# uPre.net
KiCad netlist of a schematic drawn in Altium Designer
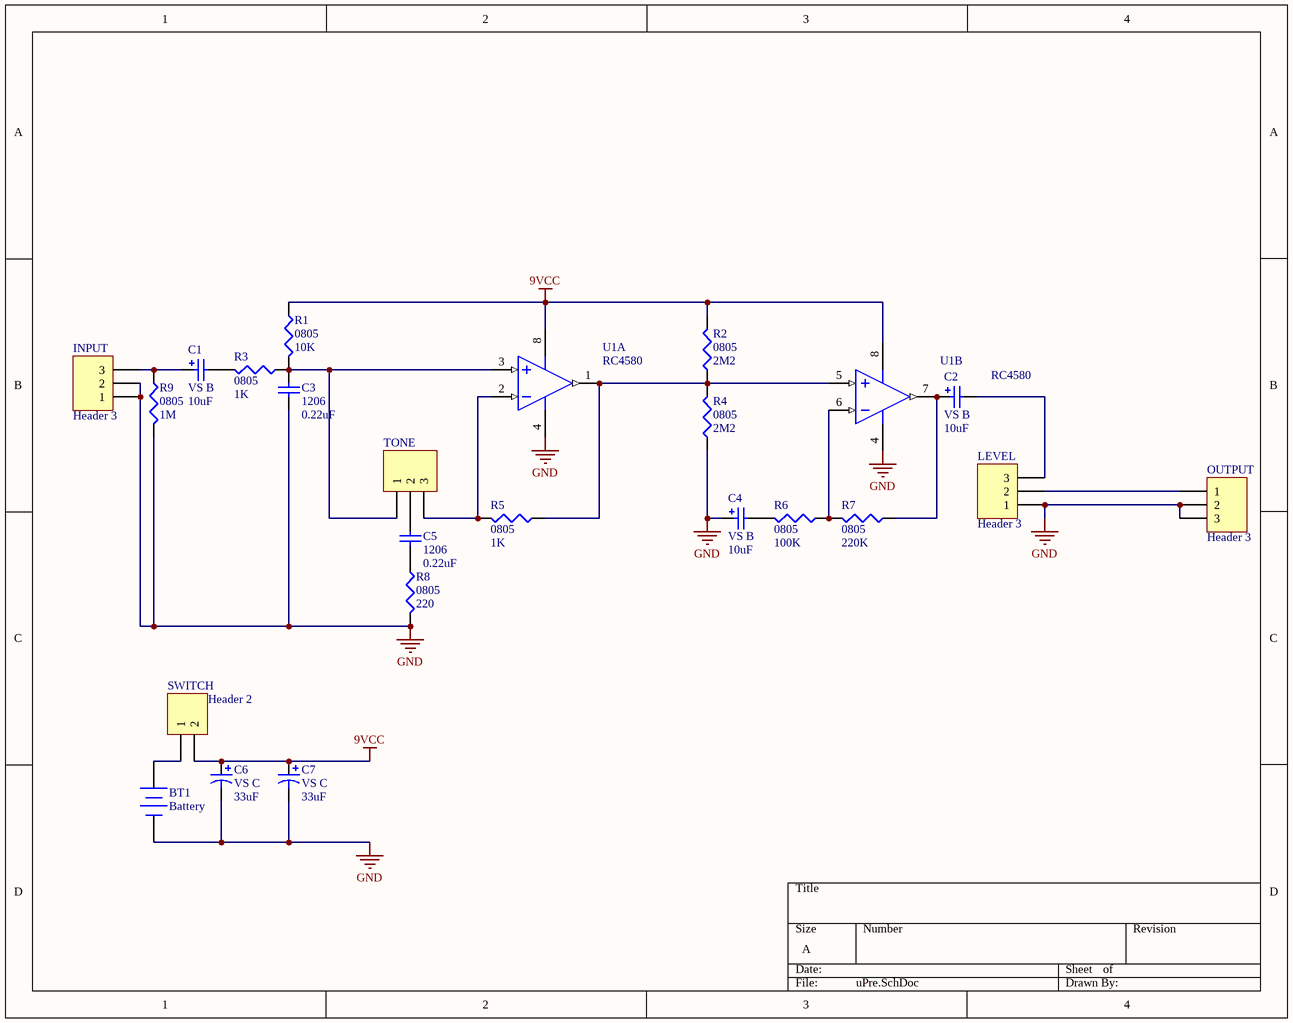
[diagram p0: uPre.SchDoc]

(export (version "E")
  (design (tool "Eeschema 10.0.6"))
  (components
    (comp (ref "BT1")
      (value "Battery")
      (footprint "BAT-2")
      (description "Multicell Battery")
      (fields (field (name "PUBLISHER") "Altium Limited"))
      (libsource (lib "Miscellaneous Devices") (part "Battery"))
    )
    (comp (ref "C1")
      (value "VS B")
      (footprint "Panasonic VS B")
      (description "Polarized Capacitor (Axial)")
      (fields (field (name "ALTIUM_VALUE") "10uF") (field (name "PUBLISHER") "Altium Limited"))
      (libsource (lib "Miscellaneous Devices") (part "Cap Pol2"))
    )
    (comp (ref "C2")
      (value "VS B")
      (footprint "Panasonic VS B")
      (description "Polarized Capacitor (Axial)")
      (fields (field (name "ALTIUM_VALUE") "10uF") (field (name "PUBLISHER") "Altium Limited"))
      (libsource (lib "Miscellaneous Devices") (part "Cap Pol2"))
    )
    (comp (ref "C3")
      (value "1206")
      (footprint "C1206")
      (description "Capacitor (Semiconductor SIM Model)")
      (fields (field (name "ALTIUM_VALUE") "0.22uF") (field (name "PUBLISHER") "Altium Limited"))
      (libsource (lib "Miscellaneous Devices") (part "Cap Semi"))
    )
    (comp (ref "C4")
      (value "VS B")
      (footprint "Panasonic VS B")
      (description "Polarized Capacitor (Axial)")
      (fields (field (name "ALTIUM_VALUE") "10uF") (field (name "PUBLISHER") "Altium Limited"))
      (libsource (lib "Miscellaneous Devices") (part "Cap Pol2"))
    )
    (comp (ref "C5")
      (value "1206")
      (footprint "C1206")
      (description "Capacitor (Semiconductor SIM Model)")
      (fields (field (name "ALTIUM_VALUE") "0.22uF") (field (name "PUBLISHER") "Altium Limited"))
      (libsource (lib "Miscellaneous Devices") (part "Cap Semi"))
    )
    (comp (ref "C6")
      (value "VS C")
      (footprint "Panasonic VS C")
      (description "Polarized Capacitor (Radial)")
      (fields (field (name "ALTIUM_VALUE") "33uF") (field (name "PUBLISHER") "Altium Limited"))
      (libsource (lib "Miscellaneous Devices") (part "Cap Pol1"))
    )
    (comp (ref "C7")
      (value "VS C")
      (footprint "Panasonic VS C")
      (description "Polarized Capacitor (Radial)")
      (fields (field (name "ALTIUM_VALUE") "33uF") (field (name "PUBLISHER") "Altium Limited"))
      (libsource (lib "Miscellaneous Devices") (part "Cap Pol1"))
    )
    (comp (ref "INPUT")
      (value "Header 3")
      (footprint "HDR1X3")
      (description "Header, 3-Pin")
      (fields (field (name "PUBLISHER") "Altium Limited"))
      (libsource (lib "") (part "Header 3_1"))
    )
    (comp (ref "LEVEL")
      (value "Header 3")
      (footprint "HDR1X3")
      (description "Header, 3-Pin")
      (fields (field (name "PUBLISHER") "Altium Limited"))
      (libsource (lib "") (part "Header 3_1"))
    )
    (comp (ref "OUTPUT")
      (value "Header 3")
      (footprint "HDR1X3")
      (description "Header, 3-Pin")
      (fields (field (name "PUBLISHER") "Altium Limited"))
      (libsource (lib "Miscellaneous Connectors") (part "Header 3"))
    )
    (comp (ref "R1")
      (value "0805")
      (footprint "SM 0805 - gap trimmed")
      (description "Resistor")
      (fields (field (name "ALTIUM_VALUE") "10K") (field (name "PUBLISHER") "Altium Limited"))
      (libsource (lib "Miscellaneous Devices") (part "Res3"))
    )
    (comp (ref "R2")
      (value "0805")
      (footprint "SM 0805 - gap trimmed")
      (description "Resistor")
      (fields (field (name "ALTIUM_VALUE") "2M2") (field (name "PUBLISHER") "Altium Limited"))
      (libsource (lib "Miscellaneous Devices") (part "Res3"))
    )
    (comp (ref "R3")
      (value "0805")
      (footprint "SM 0805 - gap trimmed")
      (description "Resistor")
      (fields (field (name "ALTIUM_VALUE") "1K") (field (name "PUBLISHER") "Altium Limited"))
      (libsource (lib "Miscellaneous Devices") (part "Res3"))
    )
    (comp (ref "R4")
      (value "0805")
      (footprint "SM 0805 - gap trimmed")
      (description "Resistor")
      (fields (field (name "ALTIUM_VALUE") "2M2") (field (name "PUBLISHER") "Altium Limited"))
      (libsource (lib "Miscellaneous Devices") (part "Res3"))
    )
    (comp (ref "R5")
      (value "0805")
      (footprint "SM 0805 - gap trimmed")
      (description "Resistor")
      (fields (field (name "ALTIUM_VALUE") "1K") (field (name "PUBLISHER") "Altium Limited"))
      (libsource (lib "Miscellaneous Devices") (part "Res3"))
    )
    (comp (ref "R6")
      (value "0805")
      (footprint "SM 0805 - gap trimmed")
      (description "Resistor")
      (fields (field (name "ALTIUM_VALUE") "100K") (field (name "PUBLISHER") "Altium Limited"))
      (libsource (lib "Miscellaneous Devices") (part "Res3"))
    )
    (comp (ref "R7")
      (value "0805")
      (footprint "SM 0805 - gap trimmed")
      (description "Resistor")
      (fields (field (name "ALTIUM_VALUE") "220K") (field (name "PUBLISHER") "Altium Limited"))
      (libsource (lib "Miscellaneous Devices") (part "Res3"))
    )
    (comp (ref "R8")
      (value "0805")
      (footprint "SM 0805 - gap trimmed")
      (description "Resistor")
      (fields (field (name "ALTIUM_VALUE") "220") (field (name "PUBLISHER") "Altium Limited"))
      (libsource (lib "Miscellaneous Devices") (part "Res3"))
    )
    (comp (ref "R9")
      (value "0805")
      (footprint "SM 0805 - gap trimmed")
      (description "Resistor")
      (fields (field (name "ALTIUM_VALUE") "1M") (field (name "PUBLISHER") "Altium Limited"))
      (libsource (lib "Miscellaneous Devices") (part "Res3"))
    )
    (comp (ref "SWITCH")
      (value "Header 2")
      (footprint "HDR1X2")
      (description "Header, 2-Pin")
      (fields (field (name "PUBLISHER") "Altium Limited"))
      (libsource (lib "Miscellaneous Connectors") (part "Header 2"))
    )
    (comp (ref "TONE")
      (value "TONE")
      (footprint "HDR1X3")
      (description "Header, 3-Pin")
      (fields (field (name "PUBLISHER") "Altium Limited"))
      (libsource (lib "") (part "Header 3_2"))
    )
    (comp (ref "U1")
      (value "RC4580")
      (footprint "SOIC127P600X175-8N")
      (description "Low Noise, High Performance, High Fidelity Dual Audio Operational Amplifier, 8-pin Narrow SOIC")
      (fields (field (name "PARTNUMBER") "LME49722MA") (field (name "MANUFACTURER") "National Semiconductor"))
      (libsource (lib "uPre Symbol Lib") (part "RC4580"))
    )
  )
  (nets
    (net (code "1") (name "9VCC") (class "Default")
      (node (ref "C6") (pin "1") (pinfunction "1_1") (pintype "passive"))
      (node (ref "C7") (pin "1") (pinfunction "1_1") (pintype "passive"))
      (node (ref "R1") (pin "1") (pinfunction "1_1") (pintype "passive"))
      (node (ref "R2") (pin "2") (pinfunction "2_2") (pintype "passive"))
      (node (ref "SWITCH") (pin "2") (pinfunction "2_2") (pintype "passive"))
      (node (ref "U1") (pin "8") (pinfunction "V+_8") (pintype "power_in"))
    )
    (net (code "2") (name "GND") (class "Default")
      (node (ref "BT1") (pin "2") (pinfunction "-_2") (pintype "passive"))
      (node (ref "C3") (pin "1") (pinfunction "1_1") (pintype "passive"))
      (node (ref "C4") (pin "1") (pinfunction "1_1") (pintype "passive"))
      (node (ref "C6") (pin "2") (pinfunction "2_2") (pintype "passive"))
      (node (ref "C7") (pin "2") (pinfunction "2_2") (pintype "passive"))
      (node (ref "INPUT") (pin "1") (pinfunction "1_1") (pintype "passive"))
      (node (ref "INPUT") (pin "2") (pinfunction "2_2") (pintype "passive"))
      (node (ref "LEVEL") (pin "1") (pinfunction "1_1") (pintype "passive"))
      (node (ref "OUTPUT") (pin "2") (pinfunction "2_2") (pintype "passive"))
      (node (ref "OUTPUT") (pin "3") (pinfunction "3_3") (pintype "passive"))
      (node (ref "R4") (pin "1") (pinfunction "1_1") (pintype "passive"))
      (node (ref "R8") (pin "2") (pinfunction "2_2") (pintype "passive"))
      (node (ref "R9") (pin "2") (pinfunction "2_2") (pintype "passive"))
      (node (ref "U1") (pin "4") (pinfunction "V-_4") (pintype "power_in"))
    )
    (net (code "3") (name "Net-(BT1-+)") (class "Default")
      (node (ref "BT1") (pin "1") (pinfunction "+_1") (pintype "passive"))
      (node (ref "SWITCH") (pin "1") (pinfunction "1_1") (pintype "passive"))
    )
    (net (code "4") (name "Net-(C1-Pad1)") (class "Default")
      (node (ref "C1") (pin "1") (pinfunction "1_1") (pintype "passive"))
      (node (ref "INPUT") (pin "3") (pinfunction "3_3") (pintype "passive"))
      (node (ref "R9") (pin "1") (pinfunction "1_1") (pintype "passive"))
    )
    (net (code "5") (name "Net-(C1-Pad2)") (class "Default")
      (node (ref "C1") (pin "2") (pinfunction "2_2") (pintype "passive"))
      (node (ref "R3") (pin "2") (pinfunction "2_2") (pintype "passive"))
    )
    (net (code "6") (name "Net-(C2-Pad2)") (class "Default")
      (node (ref "C2") (pin "2") (pinfunction "2_2") (pintype "passive"))
      (node (ref "LEVEL") (pin "3") (pinfunction "3_3") (pintype "passive"))
    )
    (net (code "7") (name "Net-(C3-Pad2)") (class "Default")
      (node (ref "C3") (pin "2") (pinfunction "2_2") (pintype "passive"))
      (node (ref "R1") (pin "2") (pinfunction "2_2") (pintype "passive"))
      (node (ref "R3") (pin "1") (pinfunction "1_1") (pintype "passive"))
      (node (ref "TONE") (pin "1") (pinfunction "1_1") (pintype "passive"))
      (node (ref "U1") (pin "3") (pinfunction "IN_A_3") (pintype "input"))
    )
    (net (code "8") (name "Net-(C4-Pad2)") (class "Default")
      (node (ref "C4") (pin "2") (pinfunction "2_2") (pintype "passive"))
      (node (ref "R6") (pin "2") (pinfunction "2_2") (pintype "passive"))
    )
    (net (code "9") (name "Net-(C5-Pad1)") (class "Default")
      (node (ref "C5") (pin "1") (pinfunction "1_1") (pintype "passive"))
      (node (ref "R8") (pin "1") (pinfunction "1_1") (pintype "passive"))
    )
    (net (code "10") (name "Net-(C5-Pad2)") (class "Default")
      (node (ref "C5") (pin "2") (pinfunction "2_2") (pintype "passive"))
      (node (ref "TONE") (pin "2") (pinfunction "2_2") (pintype "passive"))
    )
    (net (code "11") (name "Net-(LEVEL-Pad2)") (class "Default")
      (node (ref "LEVEL") (pin "2") (pinfunction "2_2") (pintype "passive"))
      (node (ref "OUTPUT") (pin "1") (pinfunction "1_1") (pintype "passive"))
    )
    (net (code "12") (name "Net-(R5-Pad2)") (class "Default")
      (node (ref "R5") (pin "2") (pinfunction "2_2") (pintype "passive"))
      (node (ref "TONE") (pin "3") (pinfunction "3_3") (pintype "passive"))
      (node (ref "U1") (pin "2") (pinfunction "IN_A_2") (pintype "input"))
    )
    (net (code "13") (name "Net-(R6-Pad1)") (class "Default")
      (node (ref "R6") (pin "1") (pinfunction "1_1") (pintype "passive"))
      (node (ref "R7") (pin "2") (pinfunction "2_2") (pintype "passive"))
      (node (ref "U1") (pin "6") (pinfunction "IN_B_6") (pintype "input"))
    )
    (net (code "14") (name "Net-(U1A-OUT_A)") (class "Default")
      (node (ref "R2") (pin "1") (pinfunction "1_1") (pintype "passive"))
      (node (ref "R4") (pin "2") (pinfunction "2_2") (pintype "passive"))
      (node (ref "R5") (pin "1") (pinfunction "1_1") (pintype "passive"))
      (node (ref "U1") (pin "1") (pinfunction "OUT_A_1") (pintype "output"))
      (node (ref "U1") (pin "5") (pinfunction "IN_B_5") (pintype "input"))
    )
    (net (code "15") (name "Net-(U1B-OUT_B)") (class "Default")
      (node (ref "C2") (pin "1") (pinfunction "1_1") (pintype "passive"))
      (node (ref "R7") (pin "1") (pinfunction "1_1") (pintype "passive"))
      (node (ref "U1") (pin "7") (pinfunction "OUT_B_7") (pintype "output"))
    )
  )
)
